# skyperobot.net
KiCad netlist of a schematic drawn in EAGLE
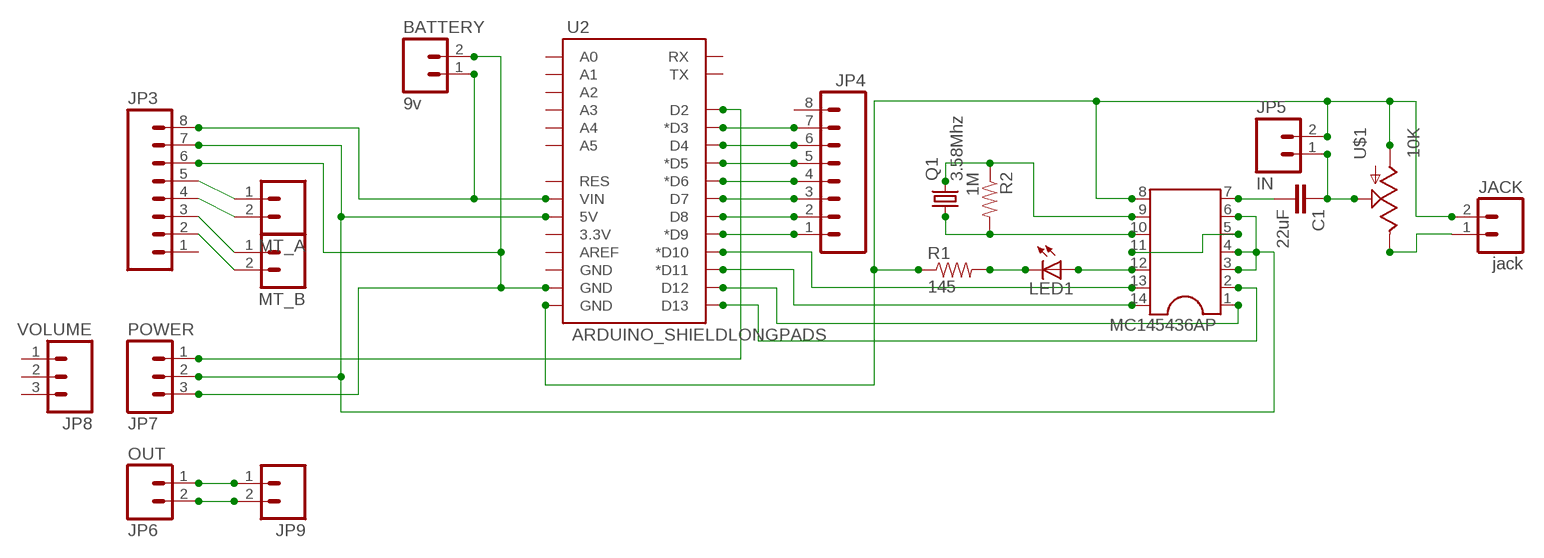
[diagram p0: schematic, sheet 1]
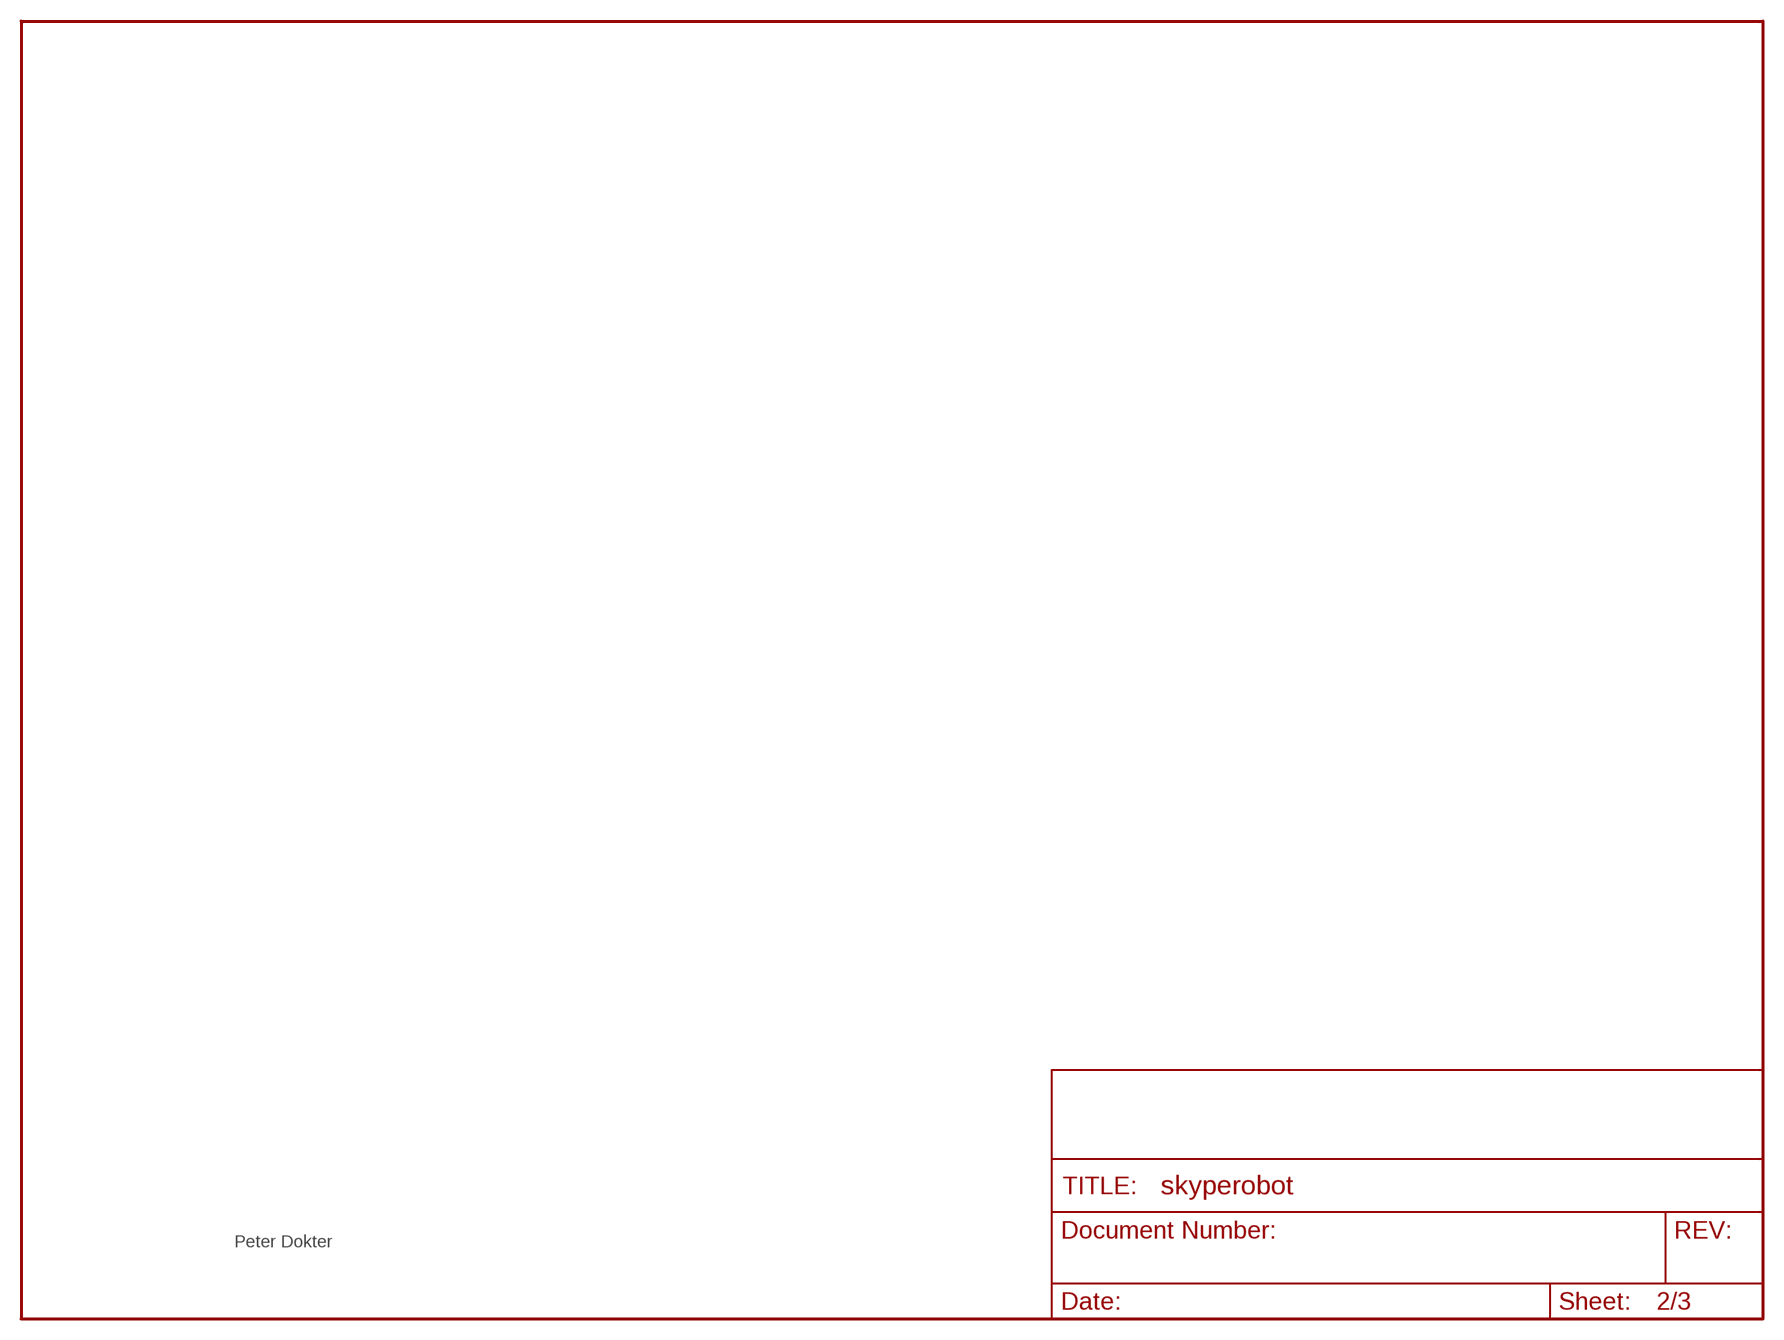
[diagram p1: schematic, sheet 2]
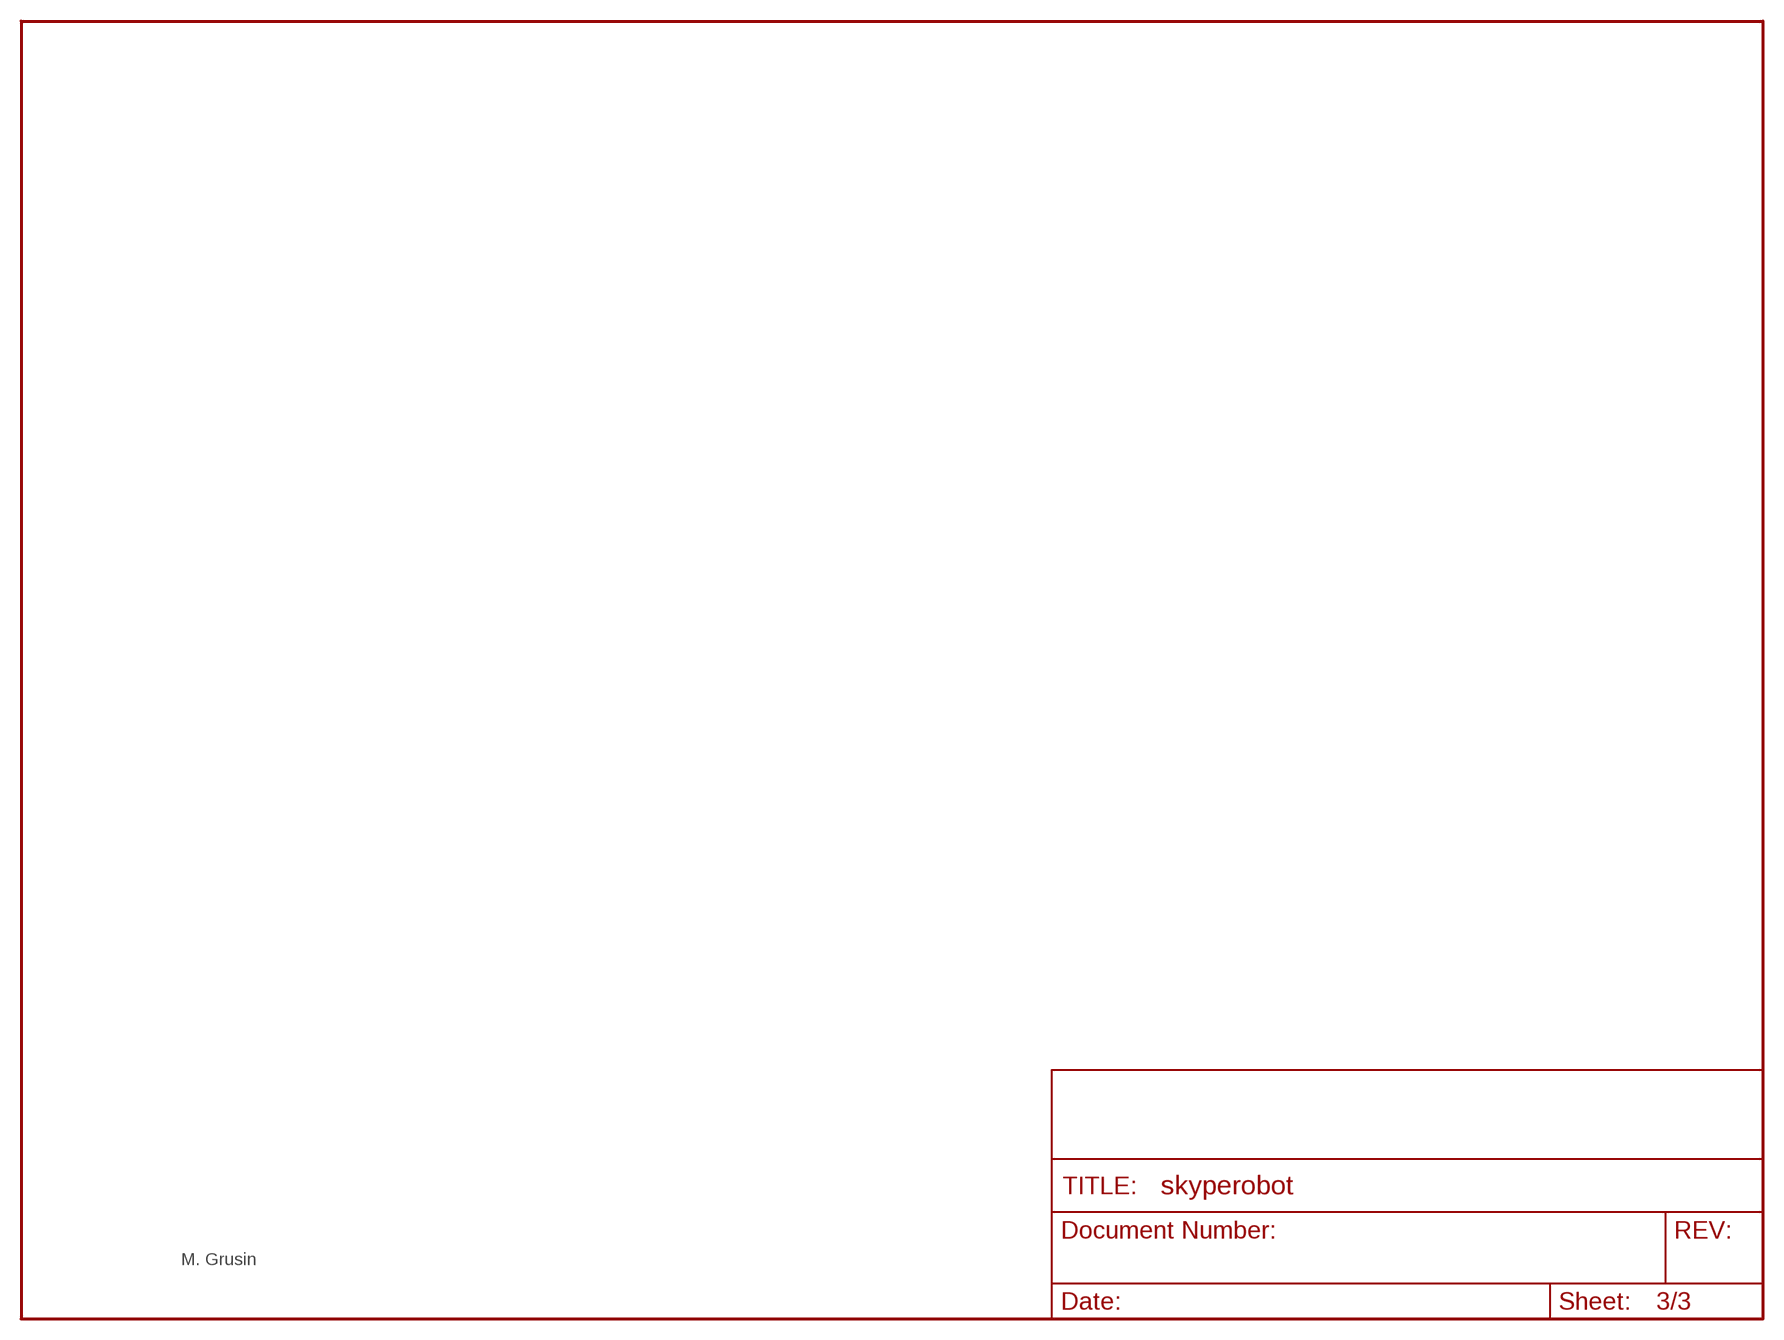
[diagram p2: schematic, sheet 3]

(export (version "E")
  (design (tool "Eeschema 10.0.6"))
  (components
    (comp (ref "BATTERY")
      (value "9v")
      (footprint "eagle-import:MOLEX-1X2")
      (libsource (lib "eagle-import") (part "M02POLAR"))
    )
    (comp (ref "C1")
      (value "22uF")
      (footprint "eagle-import:CAP-PTH-SMALL")
      (libsource (lib "eagle-import") (part "CAPPTH"))
    )
    (comp (ref "JACK")
      (value "jack")
      (footprint "eagle-import:1X02_LOCK_LONGPADS")
      (libsource (lib "eagle-import") (part "M02LOCK_LONGPADS"))
    )
    (comp (ref "JP3")
      (value "M08LONGPADS")
      (footprint "eagle-import:1X08_LONGPADS")
      (libsource (lib "eagle-import") (part "M08LONGPADS"))
    )
    (comp (ref "JP4")
      (value "M08LONGPADS")
      (footprint "eagle-import:1X08_LONGPADS")
      (libsource (lib "eagle-import") (part "M08LONGPADS"))
    )
    (comp (ref "JP5")
      (value "IN")
      (footprint "eagle-import:1X02")
      (libsource (lib "eagle-import") (part "M02PTH"))
    )
    (comp (ref "JP6")
      (value "OUT")
      (footprint "eagle-import:1X02")
      (libsource (lib "eagle-import") (part "M02PTH"))
    )
    (comp (ref "JP7")
      (value "POWER")
      (footprint "eagle-import:1X03")
      (libsource (lib "eagle-import") (part "M03PTH"))
    )
    (comp (ref "JP8")
      (value "VOLUME")
      (footprint "eagle-import:1X03")
      (libsource (lib "eagle-import") (part "M03PTH"))
    )
    (comp (ref "JP9")
      (value "M02POLAR")
      (footprint "eagle-import:MOLEX-1X2")
      (libsource (lib "eagle-import") (part "M02POLAR"))
    )
    (comp (ref "LED1")
      (value "LED3MM")
      (footprint "eagle-import:LED3MM")
      (libsource (lib "eagle-import") (part "LED3MM"))
    )
    (comp (ref "MC145436AP")
      (value "DIL14")
      (footprint "eagle-import:DIL14")
      (libsource (lib "eagle-import") (part "DIL14"))
    )
    (comp (ref "MT_A")
      (value "M02POLAR")
      (footprint "eagle-import:MOLEX-1X2")
      (libsource (lib "eagle-import") (part "M02POLAR"))
    )
    (comp (ref "MT_B")
      (value "M02POLAR")
      (footprint "eagle-import:MOLEX-1X2")
      (libsource (lib "eagle-import") (part "M02POLAR"))
    )
    (comp (ref "Q1")
      (value "3.58Mhz")
      (footprint "eagle-import:HC18U-H")
      (libsource (lib "eagle-import") (part "CRYSTALHC18U-H"))
    )
    (comp (ref "R1")
      (value "145")
      (footprint "eagle-import:AXIAL-0.3")
      (libsource (lib "eagle-import") (part "RESISTORAXIAL-0.3"))
    )
    (comp (ref "R2")
      (value "1M")
      (footprint "eagle-import:AXIAL-0.3")
      (libsource (lib "eagle-import") (part "RESISTORAXIAL-0.3"))
    )
    (comp (ref "U$1")
      (value "10K")
      (footprint "eagle-import:TRIM_POT_10MM")
      (libsource (lib "eagle-import") (part "POTTRIM"))
    )
    (comp (ref "U2")
      (value "ARDUINO_SHIELDLONGPADS")
      (footprint "eagle-import:DUEMILANOVE_SHIELD_LONGPADS_NOHOLES")
      (libsource (lib "eagle-import") (part "ARDUINO_SHIELDLONGPADS"))
    )
  )
  (nets
    (net (code "1") (name "Net-(BATTERY-Pad1)") (class "Default")
      (node (ref "BATTERY") (pin "1") (pinfunction "1_1") (pintype "passive"))
      (node (ref "JP3") (pin "8") (pinfunction "8_8") (pintype "passive"))
      (node (ref "U2") (pin "VIN") (pinfunction "VIN_VIN") (pintype "bidirectional"))
    )
    (net (code "2") (name "Net-(BATTERY-Pad2)") (class "Default")
      (node (ref "BATTERY") (pin "2") (pinfunction "2_2") (pintype "passive"))
      (node (ref "JP3") (pin "6") (pinfunction "6_6") (pintype "passive"))
      (node (ref "JP7") (pin "3") (pinfunction "3_3") (pintype "passive"))
      (node (ref "U2") (pin "GND@1") (pinfunction "GND_GND@1") (pintype "bidirectional"))
    )
    (net (code "3") (name "Net-(C1-Pad2)") (class "Default")
      (node (ref "C1") (pin "2") (pinfunction "2_2") (pintype "passive"))
      (node (ref "MC145436AP") (pin "7") (pinfunction "7_7") (pintype "passive"))
    )
    (net (code "4") (name "Net-(JP3-Pad2)") (class "Default")
      (node (ref "JP3") (pin "2") (pinfunction "2_2") (pintype "passive"))
      (node (ref "MT_B") (pin "2") (pinfunction "2_2") (pintype "passive"))
    )
    (net (code "5") (name "Net-(JP3-Pad3)") (class "Default")
      (node (ref "JP3") (pin "3") (pinfunction "3_3") (pintype "passive"))
      (node (ref "MT_B") (pin "1") (pinfunction "1_1") (pintype "passive"))
    )
    (net (code "6") (name "Net-(JP3-Pad4)") (class "Default")
      (node (ref "JP3") (pin "4") (pinfunction "4_4") (pintype "passive"))
      (node (ref "MT_A") (pin "2") (pinfunction "2_2") (pintype "passive"))
    )
    (net (code "7") (name "Net-(JP3-Pad5)") (class "Default")
      (node (ref "JP3") (pin "5") (pinfunction "5_5") (pintype "passive"))
      (node (ref "MT_A") (pin "1") (pinfunction "1_1") (pintype "passive"))
    )
    (net (code "8") (name "Net-(JP3-Pad7)") (class "Default")
      (node (ref "JP3") (pin "7") (pinfunction "7_7") (pintype "passive"))
      (node (ref "JP7") (pin "2") (pinfunction "2_2") (pintype "passive"))
      (node (ref "MC145436AP") (pin "3") (pinfunction "3_3") (pintype "passive"))
      (node (ref "MC145436AP") (pin "4") (pinfunction "4_4") (pintype "passive"))
      (node (ref "MC145436AP") (pin "6") (pinfunction "6_6") (pintype "passive"))
      (node (ref "U2") (pin "5V") (pinfunction "5V_5V") (pintype "bidirectional"))
    )
    (net (code "9") (name "Net-(JP4-Pad2)") (class "Default")
      (node (ref "JP4") (pin "2") (pinfunction "2_2") (pintype "passive"))
      (node (ref "U2") (pin "D8") (pinfunction "D8_D8") (pintype "bidirectional"))
    )
    (net (code "10") (name "Net-(JP4-Pad3)") (class "Default")
      (node (ref "JP4") (pin "3") (pinfunction "3_3") (pintype "passive"))
      (node (ref "U2") (pin "D7") (pinfunction "D7_D7") (pintype "bidirectional"))
    )
    (net (code "11") (name "Net-(JP4-Pad6)") (class "Default")
      (node (ref "JP4") (pin "6") (pinfunction "6_6") (pintype "passive"))
      (node (ref "U2") (pin "D4") (pinfunction "D4_D4") (pintype "bidirectional"))
    )
    (net (code "12") (name "Net-(JP6-Pad1)") (class "Default")
      (node (ref "JP6") (pin "1") (pinfunction "1_1") (pintype "passive"))
      (node (ref "JP9") (pin "1") (pinfunction "1_1") (pintype "passive"))
    )
    (net (code "13") (name "Net-(JP6-Pad2)") (class "Default")
      (node (ref "JP6") (pin "2") (pinfunction "2_2") (pintype "passive"))
      (node (ref "JP9") (pin "2") (pinfunction "2_2") (pintype "passive"))
    )
    (net (code "14") (name "Net-(JP7-Pad1)") (class "Default")
      (node (ref "JP7") (pin "1") (pinfunction "1_1") (pintype "passive"))
      (node (ref "U2") (pin "D2") (pinfunction "D2_D2") (pintype "bidirectional"))
    )
    (net (code "15") (name "Net-(LED1-C)") (class "Default")
      (node (ref "LED1") (pin "K") (pinfunction "C_K") (pintype "passive"))
      (node (ref "R1") (pin "P$2") (pinfunction "2_P$2") (pintype "passive"))
    )
    (net (code "16") (name "Net-(LED1-PadA)") (class "Default")
      (node (ref "LED1") (pin "A") (pinfunction "A_A") (pintype "passive"))
      (node (ref "MC145436AP") (pin "12") (pinfunction "12_12") (pintype "passive"))
    )
    (net (code "17") (name "Net-(MC145436AP-Pad1)") (class "Default")
      (node (ref "MC145436AP") (pin "1") (pinfunction "1_1") (pintype "passive"))
      (node (ref "U2") (pin "D12") (pinfunction "D12_D12") (pintype "bidirectional"))
    )
    (net (code "18") (name "Net-(MC145436AP-Pad2)") (class "Default")
      (node (ref "MC145436AP") (pin "2") (pinfunction "2_2") (pintype "passive"))
      (node (ref "U2") (pin "D13") (pinfunction "D13_D13") (pintype "bidirectional"))
    )
    (net (code "19") (name "Net-(MC145436AP-Pad11)") (class "Default")
      (node (ref "MC145436AP") (pin "11") (pinfunction "11_11") (pintype "passive"))
      (node (ref "MC145436AP") (pin "5") (pinfunction "5_5") (pintype "passive"))
    )
    (net (code "20") (name "Net-(R1-1)") (class "Default")
      (node (ref "JACK") (pin "2") (pinfunction "2_2") (pintype "passive"))
      (node (ref "JP5") (pin "2") (pinfunction "2_2") (pintype "passive"))
      (node (ref "MC145436AP") (pin "8") (pinfunction "8_8") (pintype "passive"))
      (node (ref "R1") (pin "P$1") (pinfunction "1_P$1") (pintype "passive"))
      (node (ref "U$1") (pin "3") (pinfunction "A_3") (pintype "passive"))
      (node (ref "U2") (pin "GND@0") (pinfunction "GND_GND@0") (pintype "bidirectional"))
    )
    (net (code "21") (name "Net-(R2-1)") (class "Default")
      (node (ref "MC145436AP") (pin "9") (pinfunction "9_9") (pintype "passive"))
      (node (ref "Q1") (pin "2") (pinfunction "2_2") (pintype "passive"))
      (node (ref "R2") (pin "P$1") (pinfunction "1_P$1") (pintype "passive"))
    )
    (net (code "22") (name "Net-(R2-2)") (class "Default")
      (node (ref "MC145436AP") (pin "10") (pinfunction "10_10") (pintype "passive"))
      (node (ref "Q1") (pin "1") (pinfunction "1_1") (pintype "passive"))
      (node (ref "R2") (pin "P$2") (pinfunction "2_P$2") (pintype "passive"))
    )
    (net (code "23") (name "Net-(U$1-E)") (class "Default")
      (node (ref "JACK") (pin "1") (pinfunction "1_1") (pintype "passive"))
      (node (ref "U$1") (pin "2") (pinfunction "E_2") (pintype "passive"))
    )
    (net (code "24") (name "Net-(U$1-S)") (class "Default")
      (node (ref "C1") (pin "1") (pinfunction "1_1") (pintype "passive"))
      (node (ref "JP5") (pin "1") (pinfunction "1_1") (pintype "passive"))
      (node (ref "U$1") (pin "1") (pinfunction "S_1") (pintype "passive"))
    )
    (net (code "25") (name "Net-(U2-*D3)") (class "Default")
      (node (ref "JP4") (pin "7") (pinfunction "7_7") (pintype "passive"))
      (node (ref "U2") (pin "D3") (pinfunction "*D3_D3") (pintype "bidirectional"))
    )
    (net (code "26") (name "Net-(U2-*D5)") (class "Default")
      (node (ref "JP4") (pin "5") (pinfunction "5_5") (pintype "passive"))
      (node (ref "U2") (pin "D5") (pinfunction "*D5_D5") (pintype "bidirectional"))
    )
    (net (code "27") (name "Net-(U2-*D6)") (class "Default")
      (node (ref "JP4") (pin "4") (pinfunction "4_4") (pintype "passive"))
      (node (ref "U2") (pin "D6") (pinfunction "*D6_D6") (pintype "bidirectional"))
    )
    (net (code "28") (name "Net-(U2-*D9)") (class "Default")
      (node (ref "JP4") (pin "1") (pinfunction "1_1") (pintype "passive"))
      (node (ref "U2") (pin "D9") (pinfunction "*D9_D9") (pintype "bidirectional"))
    )
    (net (code "29") (name "Net-(U2-*D10)") (class "Default")
      (node (ref "MC145436AP") (pin "13") (pinfunction "13_13") (pintype "passive"))
      (node (ref "U2") (pin "D10") (pinfunction "*D10_D10") (pintype "bidirectional"))
    )
    (net (code "30") (name "Net-(U2-*D11)") (class "Default")
      (node (ref "MC145436AP") (pin "14") (pinfunction "14_14") (pintype "passive"))
      (node (ref "U2") (pin "D11") (pinfunction "*D11_D11") (pintype "bidirectional"))
    )
    (net (code "31") (name "unconnected-(JP3-Pad1)") (class "Default")
      (node (ref "JP3") (pin "1") (pinfunction "1_1") (pintype "passive"))
    )
    (net (code "32") (name "unconnected-(JP4-Pad8)") (class "Default")
      (node (ref "JP4") (pin "8") (pinfunction "8_8") (pintype "passive"))
    )
    (net (code "33") (name "unconnected-(JP8-Pad1)") (class "Default")
      (node (ref "JP8") (pin "1") (pinfunction "1_1") (pintype "passive"))
    )
    (net (code "34") (name "unconnected-(JP8-Pad2)") (class "Default")
      (node (ref "JP8") (pin "2") (pinfunction "2_2") (pintype "passive"))
    )
    (net (code "35") (name "unconnected-(JP8-Pad3)") (class "Default")
      (node (ref "JP8") (pin "3") (pinfunction "3_3") (pintype "passive"))
    )
    (net (code "36") (name "unconnected-(U2-GND-PadGND@2)") (class "Default")
      (node (ref "U2") (pin "GND@2") (pinfunction "GND_GND@2") (pintype "bidirectional"))
    )
    (net (code "37") (name "unconnected-(U2-Pad3.3V)") (class "Default")
      (node (ref "U2") (pin "3.3V") (pinfunction "3.3V_3.3V") (pintype "bidirectional"))
    )
    (net (code "38") (name "unconnected-(U2-PadA0)") (class "Default")
      (node (ref "U2") (pin "A0") (pinfunction "A0_A0") (pintype "bidirectional"))
    )
    (net (code "39") (name "unconnected-(U2-PadA1)") (class "Default")
      (node (ref "U2") (pin "A1") (pinfunction "A1_A1") (pintype "bidirectional"))
    )
    (net (code "40") (name "unconnected-(U2-PadA2)") (class "Default")
      (node (ref "U2") (pin "A2") (pinfunction "A2_A2") (pintype "bidirectional"))
    )
    (net (code "41") (name "unconnected-(U2-PadA3)") (class "Default")
      (node (ref "U2") (pin "A3") (pinfunction "A3_A3") (pintype "bidirectional"))
    )
    (net (code "42") (name "unconnected-(U2-PadA4)") (class "Default")
      (node (ref "U2") (pin "A4") (pinfunction "A4_A4") (pintype "bidirectional"))
    )
    (net (code "43") (name "unconnected-(U2-PadA5)") (class "Default")
      (node (ref "U2") (pin "A5") (pinfunction "A5_A5") (pintype "bidirectional"))
    )
    (net (code "44") (name "unconnected-(U2-PadAREF)") (class "Default")
      (node (ref "U2") (pin "AREF") (pinfunction "AREF_AREF") (pintype "bidirectional"))
    )
    (net (code "45") (name "unconnected-(U2-PadRES)") (class "Default")
      (node (ref "U2") (pin "RES") (pinfunction "RES_RES") (pintype "bidirectional"))
    )
    (net (code "46") (name "unconnected-(U2-PadRX)") (class "Default")
      (node (ref "U2") (pin "RX") (pinfunction "RX_RX") (pintype "bidirectional"))
    )
    (net (code "47") (name "unconnected-(U2-PadTX)") (class "Default")
      (node (ref "U2") (pin "TX") (pinfunction "TX_TX") (pintype "bidirectional"))
    )
  )
)
